# Output.net
KiCad netlist of a schematic drawn in Altium Designer
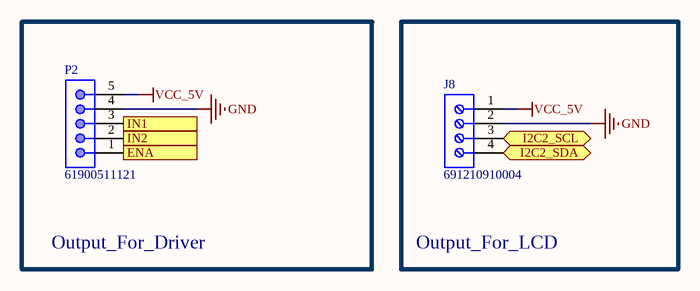
[diagram p0: Output.SchDoc]

(export (version "E")
  (design (tool "Eeschema 10.0.6"))
  (components
    (comp (ref "J8")
      (value "691210910004")
      (footprint "691210910004")
      (description "WR-TBL Serie 2109 Horizontal Entry, Rising Cage Clamp, pitch 2.54mm, 4p")
      (fields (field (name "PUBLISHER") "Wurth Elektronik"))
      (libsource (lib "691322310002.") (part "691210910004"))
    )
    (comp (ref "P2")
      (value "61900511121")
      (footprint "61900511121")
      (description "WR-WTB THT Male Vertical Locking Header, pitch 2.54mm, 5p")
      (fields (field (name "PUBLISHER") "Wurth Elektronik"))
      (libsource (lib "653008114822_Altium_WR-WTB_rev20a") (part "61900511121"))
    )
  )
  (nets
    (net (code "1") (name "/ENA") (class "Default")
      (node (ref "P2") (pin "1") (pinfunction "1_1") (pintype "passive"))
    )
    (net (code "2") (name "/I2C2_SCL") (class "Default")
      (node (ref "J8") (pin "3") (pinfunction "3_3") (pintype "passive"))
    )
    (net (code "3") (name "/I2C2_SDA") (class "Default")
      (node (ref "J8") (pin "4") (pinfunction "4_4") (pintype "passive"))
    )
    (net (code "4") (name "/IN1") (class "Default")
      (node (ref "P2") (pin "3") (pinfunction "3_3") (pintype "passive"))
    )
    (net (code "5") (name "/IN2") (class "Default")
      (node (ref "P2") (pin "2") (pinfunction "2_2") (pintype "passive"))
    )
    (net (code "6") (name "GND") (class "Default")
      (node (ref "J8") (pin "2") (pinfunction "2_2") (pintype "passive"))
      (node (ref "P2") (pin "4") (pinfunction "4_4") (pintype "passive"))
    )
    (net (code "7") (name "VCC_5V") (class "Default")
      (node (ref "J8") (pin "1") (pinfunction "1_1") (pintype "passive"))
      (node (ref "P2") (pin "5") (pinfunction "5_5") (pintype "passive"))
    )
  )
)
